# GSMMHMSlim.net
KiCad netlist of a schematic drawn in Altium Designer
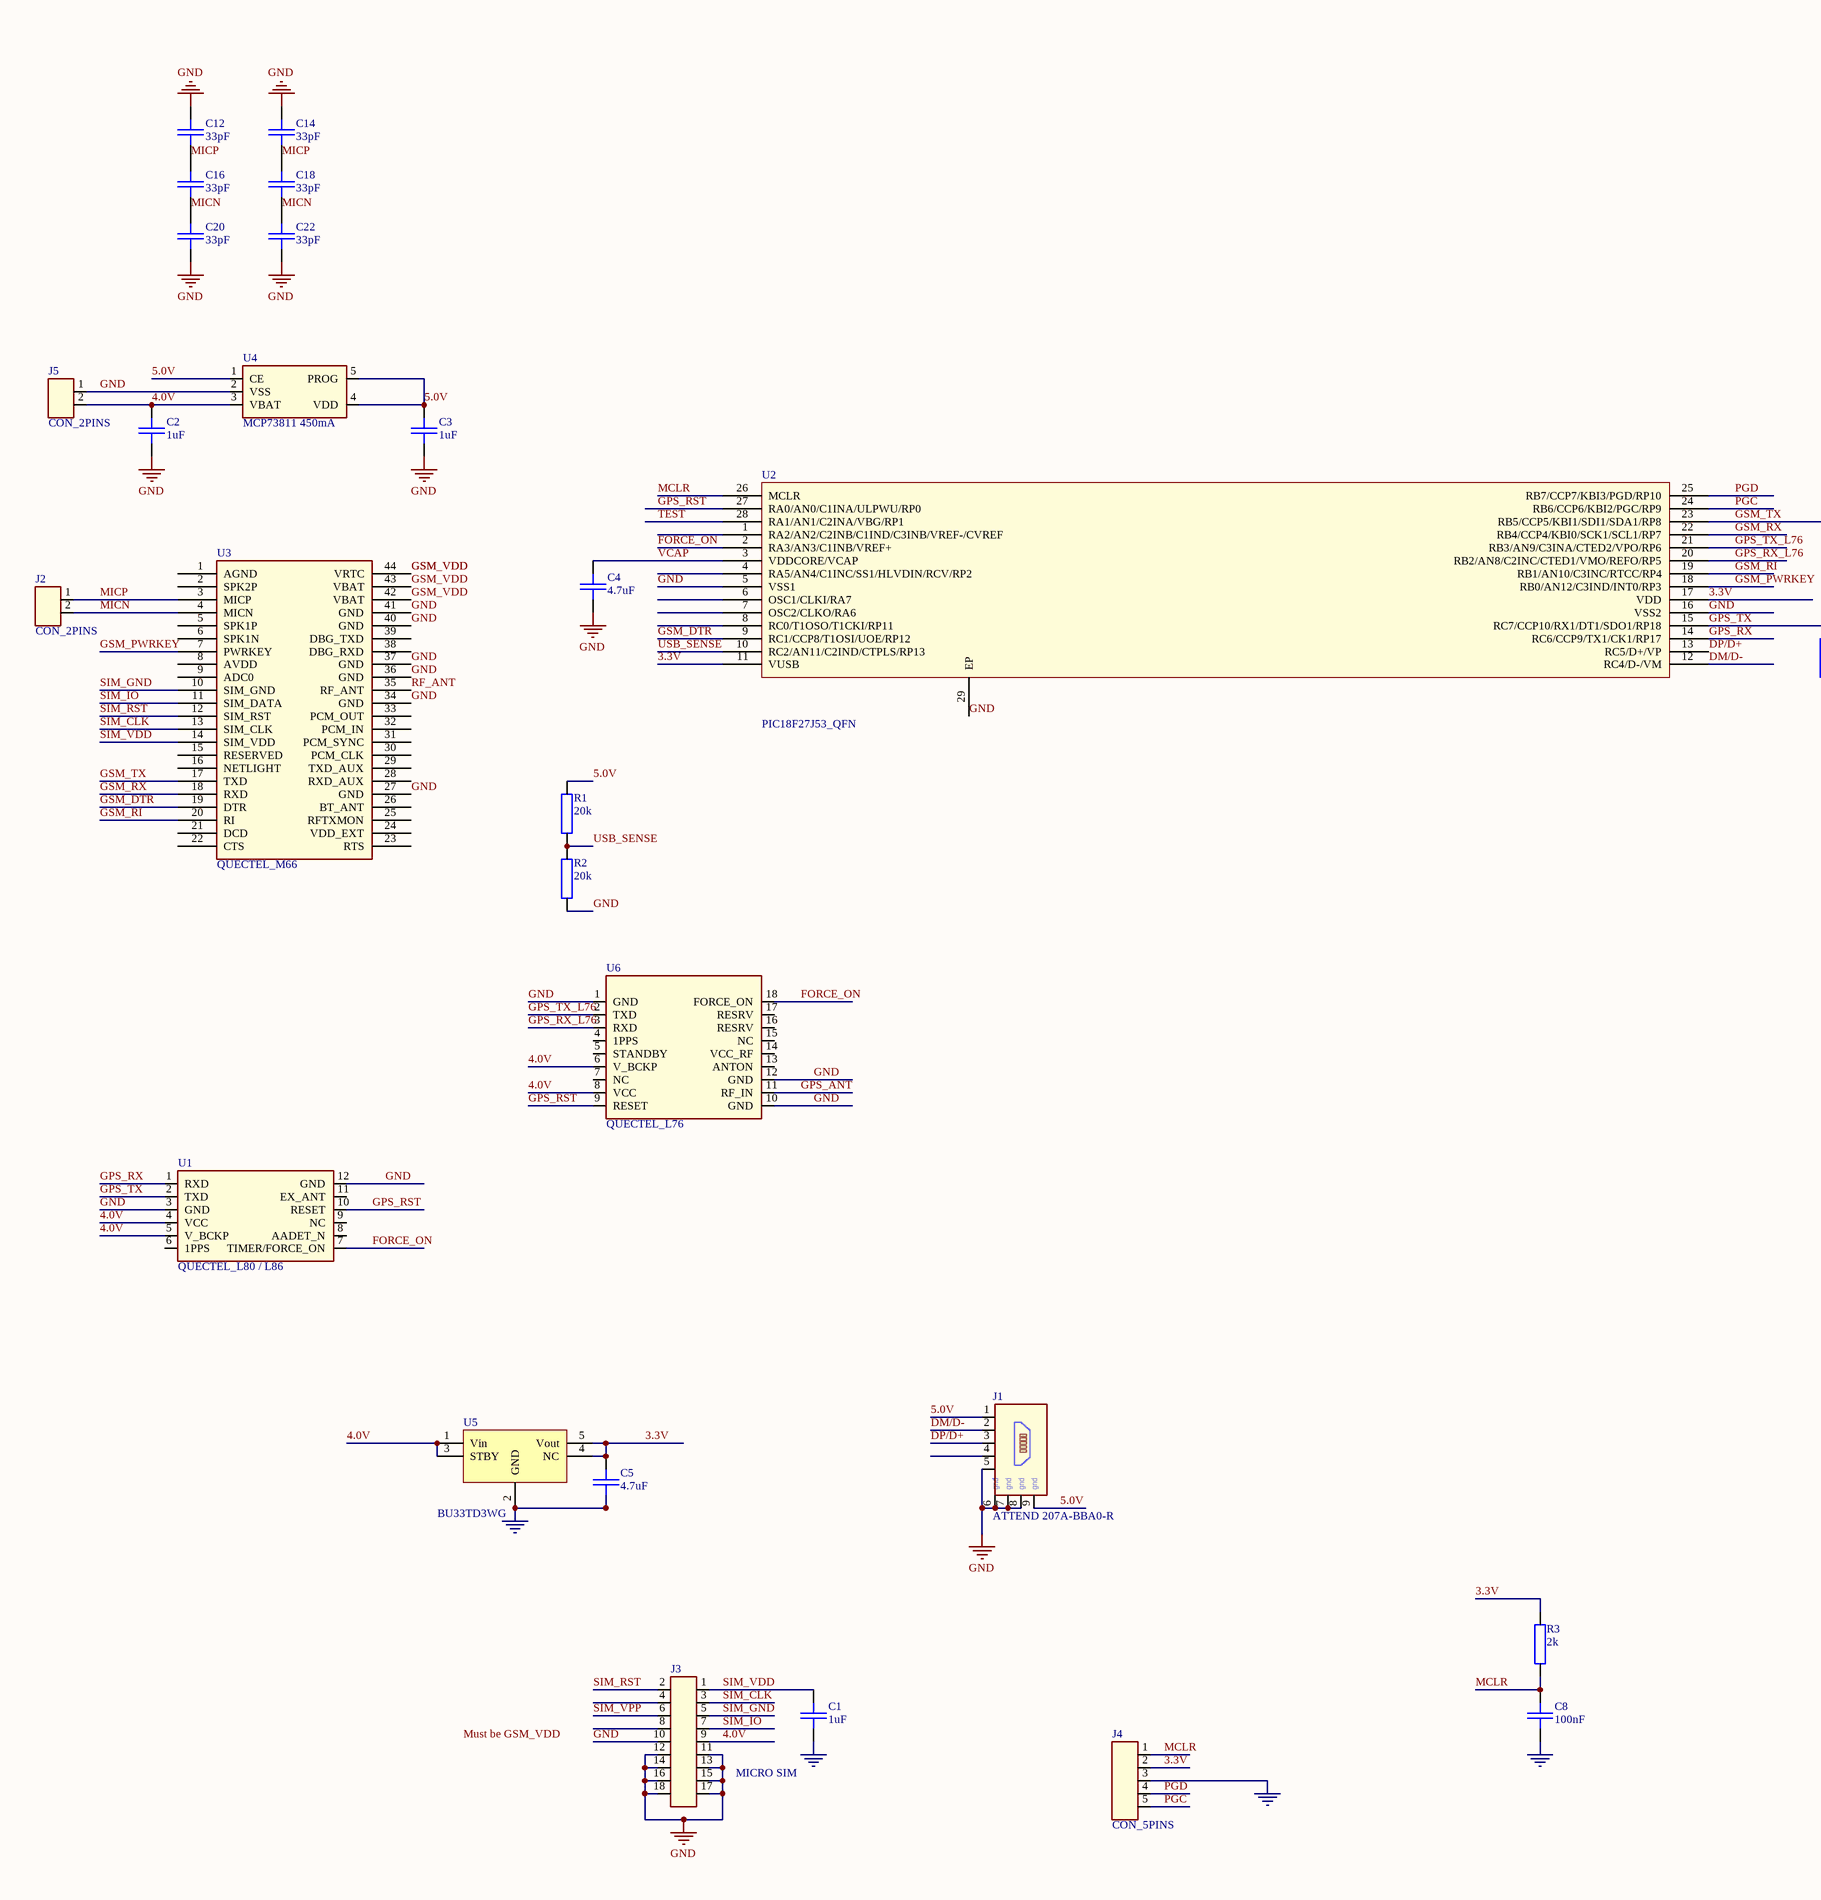
[diagram p0: GSMMHMSlim.SchDoc, left]
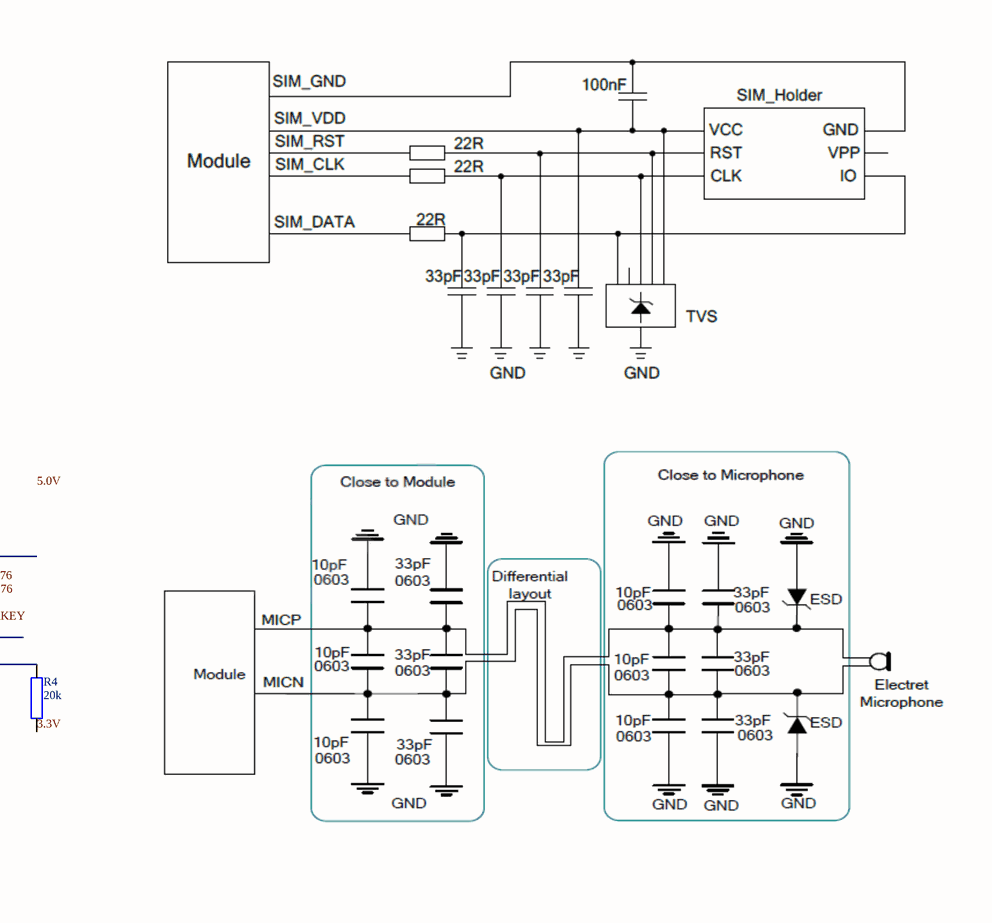
[diagram p1: GSMMHMSlim.SchDoc, right]

(export (version "E")
  (design (tool "Eeschema 10.0.6"))
  (components
    (comp (ref "C1") (value "1uF") (footprint "SMD_0603_CAPC1608X95N") (libsource (lib "DLV") (part "C")))
    (comp (ref "C2") (value "1uF") (footprint "SMD_0603_CAPC1608X95N") (libsource (lib "DLV") (part "C")))
    (comp (ref "C3") (value "1uF") (footprint "SMD_0603_CAPC1608X95N") (libsource (lib "DLV") (part "C")))
    (comp (ref "C4") (value "4.7uF") (footprint "SMD_0603_CAPC1608X95N") (libsource (lib "DLV") (part "C")))
    (comp (ref "C5") (value "4.7uF") (footprint "SMD_0603_CAPC1608X95N") (libsource (lib "DLV") (part "C")))
    (comp (ref "C8") (value "100nF") (footprint "SMD_0603_CAPC1608X95N") (libsource (lib "DLV") (part "C")))
    (comp (ref "C12") (value "33pF") (footprint "SMD_0603_CAPC1608X95N") (libsource (lib "DLV") (part "C")))
    (comp (ref "C14") (value "33pF") (footprint "SMD_0603_CAPC1608X95N") (libsource (lib "DLV") (part "C")))
    (comp (ref "C16") (value "33pF") (footprint "SMD_0603_CAPC1608X95N") (libsource (lib "DLV") (part "C")))
    (comp (ref "C18") (value "33pF") (footprint "SMD_0603_CAPC1608X95N") (libsource (lib "DLV") (part "C")))
    (comp (ref "C20") (value "33pF") (footprint "SMD_0603_CAPC1608X95N") (libsource (lib "DLV") (part "C")))
    (comp (ref "C22") (value "33pF") (footprint "SMD_0603_CAPC1608X95N") (libsource (lib "DLV") (part "C")))
    (comp (ref "J1")
      (value "ATTEND 207A-BBA0-R")
      (footprint "SMD_CON_MICRO_USB")
      (libsource (lib "DLV") (part "CON_USB_MINI"))
    )
    (comp (ref "J2")
      (value "CON_2PINS")
      (footprint "PTH_MIC_6MM_2.7MM_PITCH1.9")
      (libsource (lib "DLV") (part "CON_2PINS"))
    )
    (comp (ref "J3")
      (value "MICRO SIM")
      (footprint "SMD_CON-WURTH_MICRO_SIM_693021010811")
      (libsource (lib "DLV") (part "CON_2ROWS_18PINS"))
    )
    (comp (ref "J4") (value "CON_5PINS") (footprint "SIP5 - PGM") (libsource (lib "DLV") (part "CON_5PINS")))
    (comp (ref "J5")
      (value "CON_2PINS")
      (footprint "PTH_HDRV02W64P254_1X02")
      (libsource (lib "DLV") (part "CON_2PINS"))
    )
    (comp (ref "R1") (value "20k") (footprint "SMD_0603_RESC1608X55N") (libsource (lib "DLV") (part "R")))
    (comp (ref "R2") (value "20k") (footprint "SMD_0603_RESC1608X55N") (libsource (lib "DLV") (part "R")))
    (comp (ref "R3") (value "2k") (footprint "SMD_0603_RESC1608X55N") (libsource (lib "DLV") (part "R")))
    (comp (ref "R4") (value "20k") (footprint "SMD_0603_RESC1608X55N") (libsource (lib "DLV") (part "R")))
    (comp (ref "U1")
      (value "QUECTEL_L80 / L86")
      (footprint "SMD_MOD_L80_SOIC254P1600X1600-12N - NO UNUSED PINS")
      (libsource (lib "DLV") (part "MOD_QUECTEL_L80_L86"))
    )
    (comp (ref "U2")
      (value "PIC18F27J53_QFN")
      (footprint "SMD_QFN65P600X600X100-29AN")
      (libsource (lib "DLV") (part "IC_PIC18F27J53_QFN"))
    )
    (comp (ref "U3")
      (value "QUECTEL_M66")
      (footprint "SMD_MOD_M66-44N - NO UNUSED PINS")
      (libsource (lib "DLV") (part "MOD_QUECTEL_M66"))
    )
    (comp (ref "U4")
      (value "MCP73811 450mA")
      (footprint "SMD_SOT26_SOT95P285X140-5N - DLV")
      (description "MCP73812")
      (fields
        (field (name "DB_PART_NUMBER") "PSU000000127")
        (field (name "DB_MANUFACTURER_PART") "ROHM        BD33KA5WF-E2")
        (field (name "DB_APPROVED_BY") "VSN")
      )
      (libsource (lib "DLV") (part "IC_MCP73812"))
    )
    (comp (ref "U5")
      (value "BU33TD3WG")
      (footprint "SMD_SOT26_SOT95P285X140-5N - DLV")
      (libsource (lib "DLV") (part "IC_BU33TD3WG"))
    )
    (comp (ref "U6")
      (value "QUECTEL_L76")
      (footprint "SMD_MOD_L76_SOIC110P970X1010-18N - NO UNUSED PINS")
      (libsource (lib "DLV") (part "MOD_QUECTEL_L76"))
    )
  )
  (nets
    (net (code "1") (name "/3.3V") (class "Default")
      (node (ref "C5") (pin "1") (pinfunction "1_1") (pintype "passive"))
      (node (ref "J4") (pin "2") (pinfunction "2_2") (pintype "passive"))
      (node (ref "R3") (pin "1") (pinfunction "1_1") (pintype "passive"))
      (node (ref "R4") (pin "1") (pinfunction "1_1") (pintype "passive"))
      (node (ref "U2") (pin "11") (pinfunction "VUSB_11") (pintype "passive"))
      (node (ref "U2") (pin "17") (pinfunction "VDD_17") (pintype "passive"))
      (node (ref "U5") (pin "4") (pinfunction "NC_4") (pintype "passive"))
      (node (ref "U5") (pin "5") (pinfunction "Vout_5") (pintype "passive"))
    )
    (net (code "2") (name "/4.0V") (class "Default")
      (node (ref "C2") (pin "1") (pinfunction "1_1") (pintype "passive"))
      (node (ref "J3") (pin "9") (pinfunction "9_9") (pintype "passive"))
      (node (ref "J5") (pin "2") (pinfunction "2_2") (pintype "passive"))
      (node (ref "U1") (pin "4") (pinfunction "VCC_4") (pintype "passive"))
      (node (ref "U1") (pin "5") (pinfunction "V_BCKP_5") (pintype "passive"))
      (node (ref "U4") (pin "3") (pinfunction "VBAT_3") (pintype "passive"))
      (node (ref "U5") (pin "1") (pinfunction "Vin_1") (pintype "passive"))
      (node (ref "U5") (pin "3") (pinfunction "STBY_3") (pintype "passive"))
      (node (ref "U6") (pin "6") (pinfunction "V_BCKP_6") (pintype "passive"))
      (node (ref "U6") (pin "8") (pinfunction "VCC_8") (pintype "passive"))
    )
    (net (code "3") (name "/5.0V") (class "Default")
      (node (ref "C3") (pin "1") (pinfunction "1_1") (pintype "passive"))
      (node (ref "J1") (pin "1") (pinfunction "1_1") (pintype "passive"))
      (node (ref "J1") (pin "9") (pinfunction "9_9") (pintype "passive"))
      (node (ref "R1") (pin "2") (pinfunction "2_2") (pintype "passive"))
      (node (ref "U4") (pin "1") (pinfunction "CE_1") (pintype "passive"))
      (node (ref "U4") (pin "4") (pinfunction "VDD_4") (pintype "passive"))
      (node (ref "U4") (pin "5") (pinfunction "PROG_5") (pintype "passive"))
    )
    (net (code "4") (name "/DM{slash}D-") (class "Default")
      (node (ref "J1") (pin "2") (pinfunction "2_2") (pintype "passive"))
      (node (ref "U2") (pin "12") (pinfunction "RC4/D-/VM_12") (pintype "passive"))
    )
    (net (code "5") (name "/DP{slash}D+") (class "Default")
      (node (ref "J1") (pin "3") (pinfunction "3_3") (pintype "passive"))
      (node (ref "U2") (pin "13") (pinfunction "RC5/D+/VP_13") (pintype "passive"))
    )
    (net (code "6") (name "/FORCE_ON") (class "Default")
      (node (ref "U1") (pin "7") (pinfunction "TIMER/FORCE_ON_7") (pintype "passive"))
      (node (ref "U2") (pin "2") (pinfunction "RA3/AN3/C1INB/VREF+_2") (pintype "passive"))
      (node (ref "U6") (pin "18") (pinfunction "FORCE_ON_18") (pintype "passive"))
    )
    (net (code "7") (name "/GPS_ANT") (class "Default")
      (node (ref "U6") (pin "11") (pinfunction "RF_IN_11") (pintype "passive"))
    )
    (net (code "8") (name "/GPS_RST") (class "Default")
      (node (ref "U1") (pin "10") (pinfunction "RESET_10") (pintype "passive"))
      (node (ref "U2") (pin "27") (pinfunction "RA0/AN0/C1INA/ULPWU/RP0_27") (pintype "passive"))
      (node (ref "U6") (pin "9") (pinfunction "RESET_9") (pintype "passive"))
    )
    (net (code "9") (name "/GPS_RX") (class "Default")
      (node (ref "U1") (pin "1") (pinfunction "RXD_1") (pintype "passive"))
      (node (ref "U2") (pin "14") (pinfunction "RC6/CCP9/TX1/CK1/RP17_14") (pintype "passive"))
    )
    (net (code "10") (name "/GPS_RX_L76") (class "Default")
      (node (ref "U2") (pin "20") (pinfunction "RB2/AN8/C2INC/CTED1/VMO/REFO/RP5_20") (pintype "passive"))
      (node (ref "U6") (pin "3") (pinfunction "RXD_3") (pintype "passive"))
    )
    (net (code "11") (name "/GPS_TX") (class "Default")
      (node (ref "R4") (pin "2") (pinfunction "2_2") (pintype "passive"))
      (node (ref "U1") (pin "2") (pinfunction "TXD_2") (pintype "passive"))
      (node (ref "U2") (pin "15") (pinfunction "RC7/CCP10/RX1/DT1/SDO1/RP18_15") (pintype "passive"))
    )
    (net (code "12") (name "/GPS_TX_L76") (class "Default")
      (node (ref "U2") (pin "21") (pinfunction "RB3/AN9/C3INA/CTED2/VPO/RP6_21") (pintype "passive"))
      (node (ref "U6") (pin "2") (pinfunction "TXD_2") (pintype "passive"))
    )
    (net (code "13") (name "/GSM_DTR") (class "Default")
      (node (ref "U2") (pin "9") (pinfunction "RC1/CCP8/T1OSI/UOE/RP12_9") (pintype "passive"))
      (node (ref "U3") (pin "19") (pinfunction "DTR_19") (pintype "passive"))
    )
    (net (code "14") (name "/GSM_PWRKEY") (class "Default")
      (node (ref "U2") (pin "18") (pinfunction "RB0/AN12/C3IND/INT0/RP3_18") (pintype "passive"))
      (node (ref "U3") (pin "7") (pinfunction "PWRKEY_7") (pintype "passive"))
    )
    (net (code "15") (name "/GSM_RI") (class "Default")
      (node (ref "U2") (pin "19") (pinfunction "RB1/AN10/C3INC/RTCC/RP4_19") (pintype "passive"))
      (node (ref "U3") (pin "20") (pinfunction "RI_20") (pintype "passive"))
    )
    (net (code "16") (name "/GSM_RX") (class "Default")
      (node (ref "U2") (pin "22") (pinfunction "RB4/CCP4/KBI0/SCK1/SCL1/RP7_22") (pintype "passive"))
      (node (ref "U3") (pin "18") (pinfunction "RXD_18") (pintype "passive"))
    )
    (net (code "17") (name "/GSM_TX") (class "Default")
      (node (ref "U2") (pin "23") (pinfunction "RB5/CCP5/KBI1/SDI1/SDA1/RP8_23") (pintype "passive"))
      (node (ref "U3") (pin "17") (pinfunction "TXD_17") (pintype "passive"))
    )
    (net (code "18") (name "/GSM_VDD") (class "Default")
      (node (ref "U3") (pin "42") (pinfunction "VBAT_42") (pintype "passive"))
      (node (ref "U3") (pin "43") (pinfunction "VBAT_43") (pintype "passive"))
      (node (ref "U3") (pin "44") (pinfunction "VRTC_44") (pintype "passive"))
    )
    (net (code "19") (name "/MCLR") (class "Default")
      (node (ref "C8") (pin "1") (pinfunction "1_1") (pintype "passive"))
      (node (ref "J4") (pin "1") (pinfunction "1_1") (pintype "passive"))
      (node (ref "R3") (pin "2") (pinfunction "2_2") (pintype "passive"))
      (node (ref "U2") (pin "26") (pinfunction "MCLR_26") (pintype "passive"))
    )
    (net (code "20") (name "/MICN") (class "Default")
      (node (ref "C16") (pin "2") (pinfunction "2_2") (pintype "passive"))
      (node (ref "C18") (pin "2") (pinfunction "2_2") (pintype "passive"))
      (node (ref "C20") (pin "1") (pinfunction "1_1") (pintype "passive"))
      (node (ref "C22") (pin "1") (pinfunction "1_1") (pintype "passive"))
      (node (ref "J2") (pin "2") (pinfunction "2_2") (pintype "passive"))
      (node (ref "U3") (pin "4") (pinfunction "MICN_4") (pintype "passive"))
    )
    (net (code "21") (name "/MICP") (class "Default")
      (node (ref "C12") (pin "2") (pinfunction "2_2") (pintype "passive"))
      (node (ref "C14") (pin "2") (pinfunction "2_2") (pintype "passive"))
      (node (ref "C16") (pin "1") (pinfunction "1_1") (pintype "passive"))
      (node (ref "C18") (pin "1") (pinfunction "1_1") (pintype "passive"))
      (node (ref "J2") (pin "1") (pinfunction "1_1") (pintype "passive"))
      (node (ref "U3") (pin "3") (pinfunction "MICP_3") (pintype "passive"))
    )
    (net (code "23") (name "/PGC") (class "Default")
      (node (ref "J4") (pin "5") (pinfunction "5_5") (pintype "passive"))
      (node (ref "U2") (pin "24") (pinfunction "RB6/CCP6/KBI2/PGC/RP9_24") (pintype "passive"))
    )
    (net (code "24") (name "/PGD") (class "Default")
      (node (ref "J4") (pin "4") (pinfunction "4_4") (pintype "passive"))
      (node (ref "U2") (pin "25") (pinfunction "RB7/CCP7/KBI3/PGD/RP10_25") (pintype "passive"))
    )
    (net (code "25") (name "/RF_ANT") (class "Default")
      (node (ref "U3") (pin "35") (pinfunction "RF_ANT_35") (pintype "passive"))
    )
    (net (code "26") (name "/SIM_CLK") (class "Default")
      (node (ref "J3") (pin "3") (pinfunction "3_3") (pintype "passive"))
      (node (ref "U3") (pin "13") (pinfunction "SIM_CLK_13") (pintype "passive"))
    )
    (net (code "27") (name "/SIM_GND") (class "Default")
      (node (ref "J3") (pin "5") (pinfunction "5_5") (pintype "passive"))
      (node (ref "U3") (pin "10") (pinfunction "SIM_GND_10") (pintype "passive"))
    )
    (net (code "28") (name "/SIM_IO") (class "Default")
      (node (ref "J3") (pin "7") (pinfunction "7_7") (pintype "passive"))
      (node (ref "U3") (pin "11") (pinfunction "SIM_DATA_11") (pintype "passive"))
    )
    (net (code "29") (name "/SIM_RST") (class "Default")
      (node (ref "J3") (pin "2") (pinfunction "2_2") (pintype "passive"))
      (node (ref "U3") (pin "12") (pinfunction "SIM_RST_12") (pintype "passive"))
    )
    (net (code "30") (name "/SIM_VDD") (class "Default")
      (node (ref "C1") (pin "1") (pinfunction "1_1") (pintype "passive"))
      (node (ref "J3") (pin "1") (pinfunction "1_1") (pintype "passive"))
      (node (ref "U3") (pin "14") (pinfunction "SIM_VDD_14") (pintype "passive"))
    )
    (net (code "31") (name "/SIM_VPP") (class "Default")
      (node (ref "J3") (pin "6") (pinfunction "6_6") (pintype "passive"))
    )
    (net (code "32") (name "/TEST") (class "Default")
      (node (ref "U2") (pin "28") (pinfunction "RA1/AN1/C2INA/VBG/RP1_28") (pintype "passive"))
    )
    (net (code "33") (name "/USB_SENSE") (class "Default")
      (node (ref "R1") (pin "1") (pinfunction "1_1") (pintype "passive"))
      (node (ref "R2") (pin "2") (pinfunction "2_2") (pintype "passive"))
      (node (ref "U2") (pin "10") (pinfunction "RC2/AN11/C2IND/CTPLS/RP13_10") (pintype "passive"))
    )
    (net (code "34") (name "/VCAP") (class "Default")
      (node (ref "C4") (pin "1") (pinfunction "1_1") (pintype "passive"))
      (node (ref "U2") (pin "3") (pinfunction "VDDCORE/VCAP_3") (pintype "passive"))
    )
    (net (code "35") (name "GND") (class "Default")
      (node (ref "C1") (pin "2") (pinfunction "2_2") (pintype "passive"))
      (node (ref "C12") (pin "1") (pinfunction "1_1") (pintype "passive"))
      (node (ref "C14") (pin "1") (pinfunction "1_1") (pintype "passive"))
      (node (ref "C2") (pin "2") (pinfunction "2_2") (pintype "passive"))
      (node (ref "C20") (pin "2") (pinfunction "2_2") (pintype "passive"))
      (node (ref "C22") (pin "2") (pinfunction "2_2") (pintype "passive"))
      (node (ref "C3") (pin "2") (pinfunction "2_2") (pintype "passive"))
      (node (ref "C4") (pin "2") (pinfunction "2_2") (pintype "passive"))
      (node (ref "C5") (pin "2") (pinfunction "2_2") (pintype "passive"))
      (node (ref "C8") (pin "2") (pinfunction "2_2") (pintype "passive"))
      (node (ref "J1") (pin "5") (pinfunction "5_5") (pintype "passive"))
      (node (ref "J1") (pin "6") (pinfunction "6_6") (pintype "passive"))
      (node (ref "J1") (pin "7") (pinfunction "7_7") (pintype "passive"))
      (node (ref "J1") (pin "8") (pinfunction "8_8") (pintype "passive"))
      (node (ref "J3") (pin "10") (pinfunction "10_10") (pintype "passive"))
      (node (ref "J3") (pin "11") (pinfunction "11_11") (pintype "passive"))
      (node (ref "J3") (pin "12") (pinfunction "12_12") (pintype "passive"))
      (node (ref "J3") (pin "13") (pinfunction "13_13") (pintype "passive"))
      (node (ref "J3") (pin "14") (pinfunction "14_14") (pintype "passive"))
      (node (ref "J3") (pin "15") (pinfunction "15_15") (pintype "passive"))
      (node (ref "J3") (pin "16") (pinfunction "16_16") (pintype "passive"))
      (node (ref "J3") (pin "17") (pinfunction "17_17") (pintype "passive"))
      (node (ref "J3") (pin "18") (pinfunction "18_18") (pintype "passive"))
      (node (ref "J4") (pin "3") (pinfunction "3_3") (pintype "passive"))
      (node (ref "J5") (pin "1") (pinfunction "1_1") (pintype "passive"))
      (node (ref "R2") (pin "1") (pinfunction "1_1") (pintype "passive"))
      (node (ref "U1") (pin "12") (pinfunction "GND_12") (pintype "passive"))
      (node (ref "U1") (pin "3") (pinfunction "GND_3") (pintype "passive"))
      (node (ref "U2") (pin "16") (pinfunction "VSS2_16") (pintype "passive"))
      (node (ref "U2") (pin "29") (pinfunction "EP_29") (pintype "passive"))
      (node (ref "U2") (pin "5") (pinfunction "VSS1_5") (pintype "passive"))
      (node (ref "U3") (pin "27") (pinfunction "GND_27") (pintype "passive"))
      (node (ref "U3") (pin "34") (pinfunction "GND_34") (pintype "passive"))
      (node (ref "U3") (pin "36") (pinfunction "GND_36") (pintype "passive"))
      (node (ref "U3") (pin "37") (pinfunction "GND_37") (pintype "passive"))
      (node (ref "U3") (pin "40") (pinfunction "GND_40") (pintype "passive"))
      (node (ref "U3") (pin "41") (pinfunction "GND_41") (pintype "passive"))
      (node (ref "U4") (pin "2") (pinfunction "VSS_2") (pintype "passive"))
      (node (ref "U5") (pin "2") (pinfunction "GND_2") (pintype "passive"))
      (node (ref "U6") (pin "1") (pinfunction "GND_1") (pintype "passive"))
      (node (ref "U6") (pin "10") (pinfunction "GND_10") (pintype "passive"))
      (node (ref "U6") (pin "12") (pinfunction "GND_12") (pintype "passive"))
    )
    (net (code "36") (name "unconnected-(J1-Pad4)") (class "Default")
      (node (ref "J1") (pin "4") (pinfunction "4_4") (pintype "passive"))
    )
    (net (code "37") (name "unconnected-(J3-Pad4)") (class "Default")
      (node (ref "J3") (pin "4") (pinfunction "4_4") (pintype "passive"))
    )
    (net (code "38") (name "unconnected-(J3-Pad8)") (class "Default")
      (node (ref "J3") (pin "8") (pinfunction "8_8") (pintype "passive"))
    )
    (net (code "39") (name "unconnected-(U1-1PPS-Pad6)") (class "Default")
      (node (ref "U1") (pin "6") (pinfunction "1PPS_6") (pintype "passive"))
    )
    (net (code "40") (name "unconnected-(U1-AADET_N-Pad8)") (class "Default")
      (node (ref "U1") (pin "8") (pinfunction "AADET_N_8") (pintype "passive"))
    )
    (net (code "41") (name "unconnected-(U1-EX_ANT-Pad11)") (class "Default")
      (node (ref "U1") (pin "11") (pinfunction "EX_ANT_11") (pintype "passive"))
    )
    (net (code "42") (name "unconnected-(U1-NC-Pad9)") (class "Default")
      (node (ref "U1") (pin "9") (pinfunction "NC_9") (pintype "passive"))
    )
    (net (code "43") (name "unconnected-(U2-OSC1{slash}CLKI{slash}RA7-Pad6)") (class "Default")
      (node (ref "U2") (pin "6") (pinfunction "OSC1/CLKI/RA7_6") (pintype "passive"))
    )
    (net (code "44") (name "unconnected-(U2-OSC2{slash}CLKO{slash}RA6-Pad7)") (class "Default")
      (node (ref "U2") (pin "7") (pinfunction "OSC2/CLKO/RA6_7") (pintype "passive"))
    )
    (net (code "45") (name "unconnected-(U2-RA2{slash}AN2{slash}C2INB{slash}C1IND{slash}C3INB{slash}VREF-{slash}CVREF-Pad1)") (class "Default")
      (node (ref "U2") (pin "1") (pinfunction "RA2/AN2/C2INB/C1IND/C3INB/VREF-/CVREF_1") (pintype "passive"))
    )
    (net (code "46") (name "unconnected-(U2-RA5{slash}AN4{slash}C1INC{slash}SS1{slash}HLVDIN{slash}RCV{slash}RP2-Pad4)") (class "Default")
      (node (ref "U2") (pin "4") (pinfunction "RA5/AN4/C1INC/SS1/HLVDIN/RCV/RP2_4") (pintype "passive"))
    )
    (net (code "47") (name "unconnected-(U2-RC0{slash}T1OSO{slash}T1CKI{slash}RP11-Pad8)") (class "Default")
      (node (ref "U2") (pin "8") (pinfunction "RC0/T1OSO/T1CKI/RP11_8") (pintype "passive"))
    )
    (net (code "48") (name "unconnected-(U3-ADC0-Pad9)") (class "Default")
      (node (ref "U3") (pin "9") (pinfunction "ADC0_9") (pintype "passive"))
    )
    (net (code "49") (name "unconnected-(U3-AGND-Pad1)") (class "Default")
      (node (ref "U3") (pin "1") (pinfunction "AGND_1") (pintype "passive"))
    )
    (net (code "50") (name "unconnected-(U3-AVDD-Pad8)") (class "Default")
      (node (ref "U3") (pin "8") (pinfunction "AVDD_8") (pintype "passive"))
    )
    (net (code "51") (name "unconnected-(U3-BT_ANT-Pad26)") (class "Default")
      (node (ref "U3") (pin "26") (pinfunction "BT_ANT_26") (pintype "passive"))
    )
    (net (code "52") (name "unconnected-(U3-CTS-Pad22)") (class "Default")
      (node (ref "U3") (pin "22") (pinfunction "CTS_22") (pintype "passive"))
    )
    (net (code "53") (name "unconnected-(U3-DBG_RXD-Pad38)") (class "Default")
      (node (ref "U3") (pin "38") (pinfunction "DBG_RXD_38") (pintype "passive"))
    )
    (net (code "54") (name "unconnected-(U3-DBG_TXD-Pad39)") (class "Default")
      (node (ref "U3") (pin "39") (pinfunction "DBG_TXD_39") (pintype "passive"))
    )
    (net (code "55") (name "unconnected-(U3-DCD-Pad21)") (class "Default")
      (node (ref "U3") (pin "21") (pinfunction "DCD_21") (pintype "passive"))
    )
    (net (code "56") (name "unconnected-(U3-NETLIGHT-Pad16)") (class "Default")
      (node (ref "U3") (pin "16") (pinfunction "NETLIGHT_16") (pintype "passive"))
    )
    (net (code "57") (name "unconnected-(U3-PCM_CLK-Pad30)") (class "Default")
      (node (ref "U3") (pin "30") (pinfunction "PCM_CLK_30") (pintype "passive"))
    )
    (net (code "58") (name "unconnected-(U3-PCM_IN-Pad32)") (class "Default")
      (node (ref "U3") (pin "32") (pinfunction "PCM_IN_32") (pintype "passive"))
    )
    (net (code "59") (name "unconnected-(U3-PCM_OUT-Pad33)") (class "Default")
      (node (ref "U3") (pin "33") (pinfunction "PCM_OUT_33") (pintype "passive"))
    )
    (net (code "60") (name "unconnected-(U3-PCM_SYNC-Pad31)") (class "Default")
      (node (ref "U3") (pin "31") (pinfunction "PCM_SYNC_31") (pintype "passive"))
    )
    (net (code "61") (name "unconnected-(U3-RESERVED-Pad15)") (class "Default")
      (node (ref "U3") (pin "15") (pinfunction "RESERVED_15") (pintype "passive"))
    )
    (net (code "62") (name "unconnected-(U3-RFTXMON-Pad25)") (class "Default")
      (node (ref "U3") (pin "25") (pinfunction "RFTXMON_25") (pintype "passive"))
    )
    (net (code "63") (name "unconnected-(U3-RTS-Pad23)") (class "Default")
      (node (ref "U3") (pin "23") (pinfunction "RTS_23") (pintype "passive"))
    )
    (net (code "64") (name "unconnected-(U3-RXD_AUX-Pad28)") (class "Default")
      (node (ref "U3") (pin "28") (pinfunction "RXD_AUX_28") (pintype "passive"))
    )
    (net (code "65") (name "unconnected-(U3-SPK1N-Pad6)") (class "Default")
      (node (ref "U3") (pin "6") (pinfunction "SPK1N_6") (pintype "passive"))
    )
    (net (code "66") (name "unconnected-(U3-SPK1P-Pad5)") (class "Default")
      (node (ref "U3") (pin "5") (pinfunction "SPK1P_5") (pintype "passive"))
    )
    (net (code "67") (name "unconnected-(U3-SPK2P-Pad2)") (class "Default")
      (node (ref "U3") (pin "2") (pinfunction "SPK2P_2") (pintype "passive"))
    )
    (net (code "68") (name "unconnected-(U3-TXD_AUX-Pad29)") (class "Default")
      (node (ref "U3") (pin "29") (pinfunction "TXD_AUX_29") (pintype "passive"))
    )
    (net (code "69") (name "unconnected-(U3-VDD_EXT-Pad24)") (class "Default")
      (node (ref "U3") (pin "24") (pinfunction "VDD_EXT_24") (pintype "passive"))
    )
    (net (code "70") (name "unconnected-(U6-1PPS-Pad4)") (class "Default")
      (node (ref "U6") (pin "4") (pinfunction "1PPS_4") (pintype "passive"))
    )
    (net (code "71") (name "unconnected-(U6-ANTON-Pad13)") (class "Default")
      (node (ref "U6") (pin "13") (pinfunction "ANTON_13") (pintype "passive"))
    )
    (net (code "72") (name "unconnected-(U6-NC-Pad7)") (class "Default")
      (node (ref "U6") (pin "7") (pinfunction "NC_7") (pintype "passive"))
    )
    (net (code "73") (name "unconnected-(U6-NC-Pad15)") (class "Default")
      (node (ref "U6") (pin "15") (pinfunction "NC_15") (pintype "passive"))
    )
    (net (code "74") (name "unconnected-(U6-RESRV-Pad16)") (class "Default")
      (node (ref "U6") (pin "16") (pinfunction "RESRV_16") (pintype "passive"))
    )
    (net (code "75") (name "unconnected-(U6-RESRV-Pad17)") (class "Default")
      (node (ref "U6") (pin "17") (pinfunction "RESRV_17") (pintype "passive"))
    )
    (net (code "76") (name "unconnected-(U6-STANDBY-Pad5)") (class "Default")
      (node (ref "U6") (pin "5") (pinfunction "STANDBY_5") (pintype "passive"))
    )
    (net (code "77") (name "unconnected-(U6-VCC_RF-Pad14)") (class "Default")
      (node (ref "U6") (pin "14") (pinfunction "VCC_RF_14") (pintype "passive"))
    )
  )
)
